# woda.net
KiCad netlist of a schematic drawn in Altium Designer
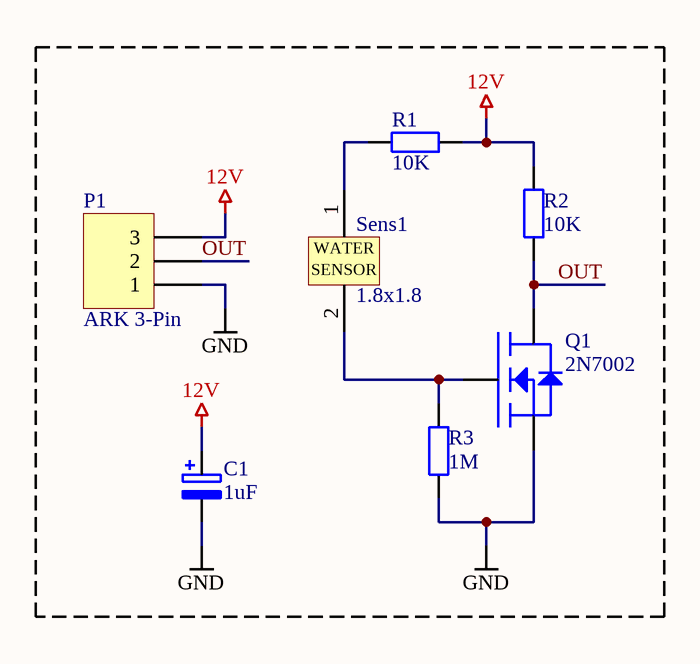
[diagram p0: woda.SchDoc]

(export (version "E")
  (design (tool "Eeschema 10.0.6"))
  (components
    (comp (ref "C1")
      (value "1uF")
      (footprint "TANC_A")
      (description "Capacitor Polarized")
      (libsource (lib "Library") (part "Cap_Pol"))
    )
    (comp (ref "P1")
      (value "ARK 3-Pin")
      (footprint "ARK-3.5mm-3pin")
      (libsource (lib "Connectors") (part "ARK 3-Pin"))
    )
    (comp (ref "Q1")
      (value "2N7002")
      (footprint "SOT23")
      (description "N-MOSFET")
      (libsource (lib "Library") (part "2N7002(GSD)"))
    )
    (comp (ref "R1")
      (value "10K")
      (footprint "R0805")
      (description "Resistor")
      (libsource (lib "") (part "Res_1"))
    )
    (comp (ref "R2")
      (value "10K")
      (footprint "R0805")
      (description "Resistor")
      (libsource (lib "Library") (part "Res"))
    )
    (comp (ref "R3")
      (value "1M")
      (footprint "R0805")
      (description "Resistor")
      (libsource (lib "Library") (part "Res"))
    )
    (comp (ref "Sens1")
      (value "1.8x1.8")
      (footprint "water_sensor")
      (libsource (lib "Library") (part "Water_sensor_1"))
    )
  )
  (nets
    (net (code "1") (name "/OUT") (class "Default")
      (node (ref "P1") (pin "2") (pinfunction "2_2") (pintype "passive"))
      (node (ref "Q1") (pin "3") (pinfunction "D_3") (pintype "passive"))
      (node (ref "R2") (pin "1") (pinfunction "1_1") (pintype "passive"))
    )
    (net (code "2") (name "12V") (class "Default")
      (node (ref "C1") (pin "1") (pinfunction "1_1") (pintype "passive"))
      (node (ref "P1") (pin "3") (pinfunction "3_3") (pintype "passive"))
      (node (ref "R1") (pin "1") (pinfunction "1_1") (pintype "passive"))
      (node (ref "R2") (pin "2") (pinfunction "2_2") (pintype "passive"))
    )
    (net (code "3") (name "GND") (class "Default")
      (node (ref "C1") (pin "2") (pinfunction "2_2") (pintype "passive"))
      (node (ref "P1") (pin "1") (pinfunction "1_1") (pintype "passive"))
      (node (ref "Q1") (pin "2") (pinfunction "S_2") (pintype "passive"))
      (node (ref "R3") (pin "1") (pinfunction "1_1") (pintype "passive"))
    )
    (net (code "4") (name "Net-(Q1-G)") (class "Default")
      (node (ref "Q1") (pin "1") (pinfunction "G_1") (pintype "passive"))
      (node (ref "R3") (pin "2") (pinfunction "2_2") (pintype "passive"))
      (node (ref "Sens1") (pin "2") (pinfunction "2_2") (pintype "power_in"))
    )
    (net (code "5") (name "Net-(R1-Pad2)") (class "Default")
      (node (ref "R1") (pin "2") (pinfunction "2_2") (pintype "passive"))
      (node (ref "Sens1") (pin "1") (pinfunction "1_1") (pintype "power_in"))
    )
  )
)
